# current_monitor_v1-2-1.net
KiCad netlist of a schematic drawn in EAGLE
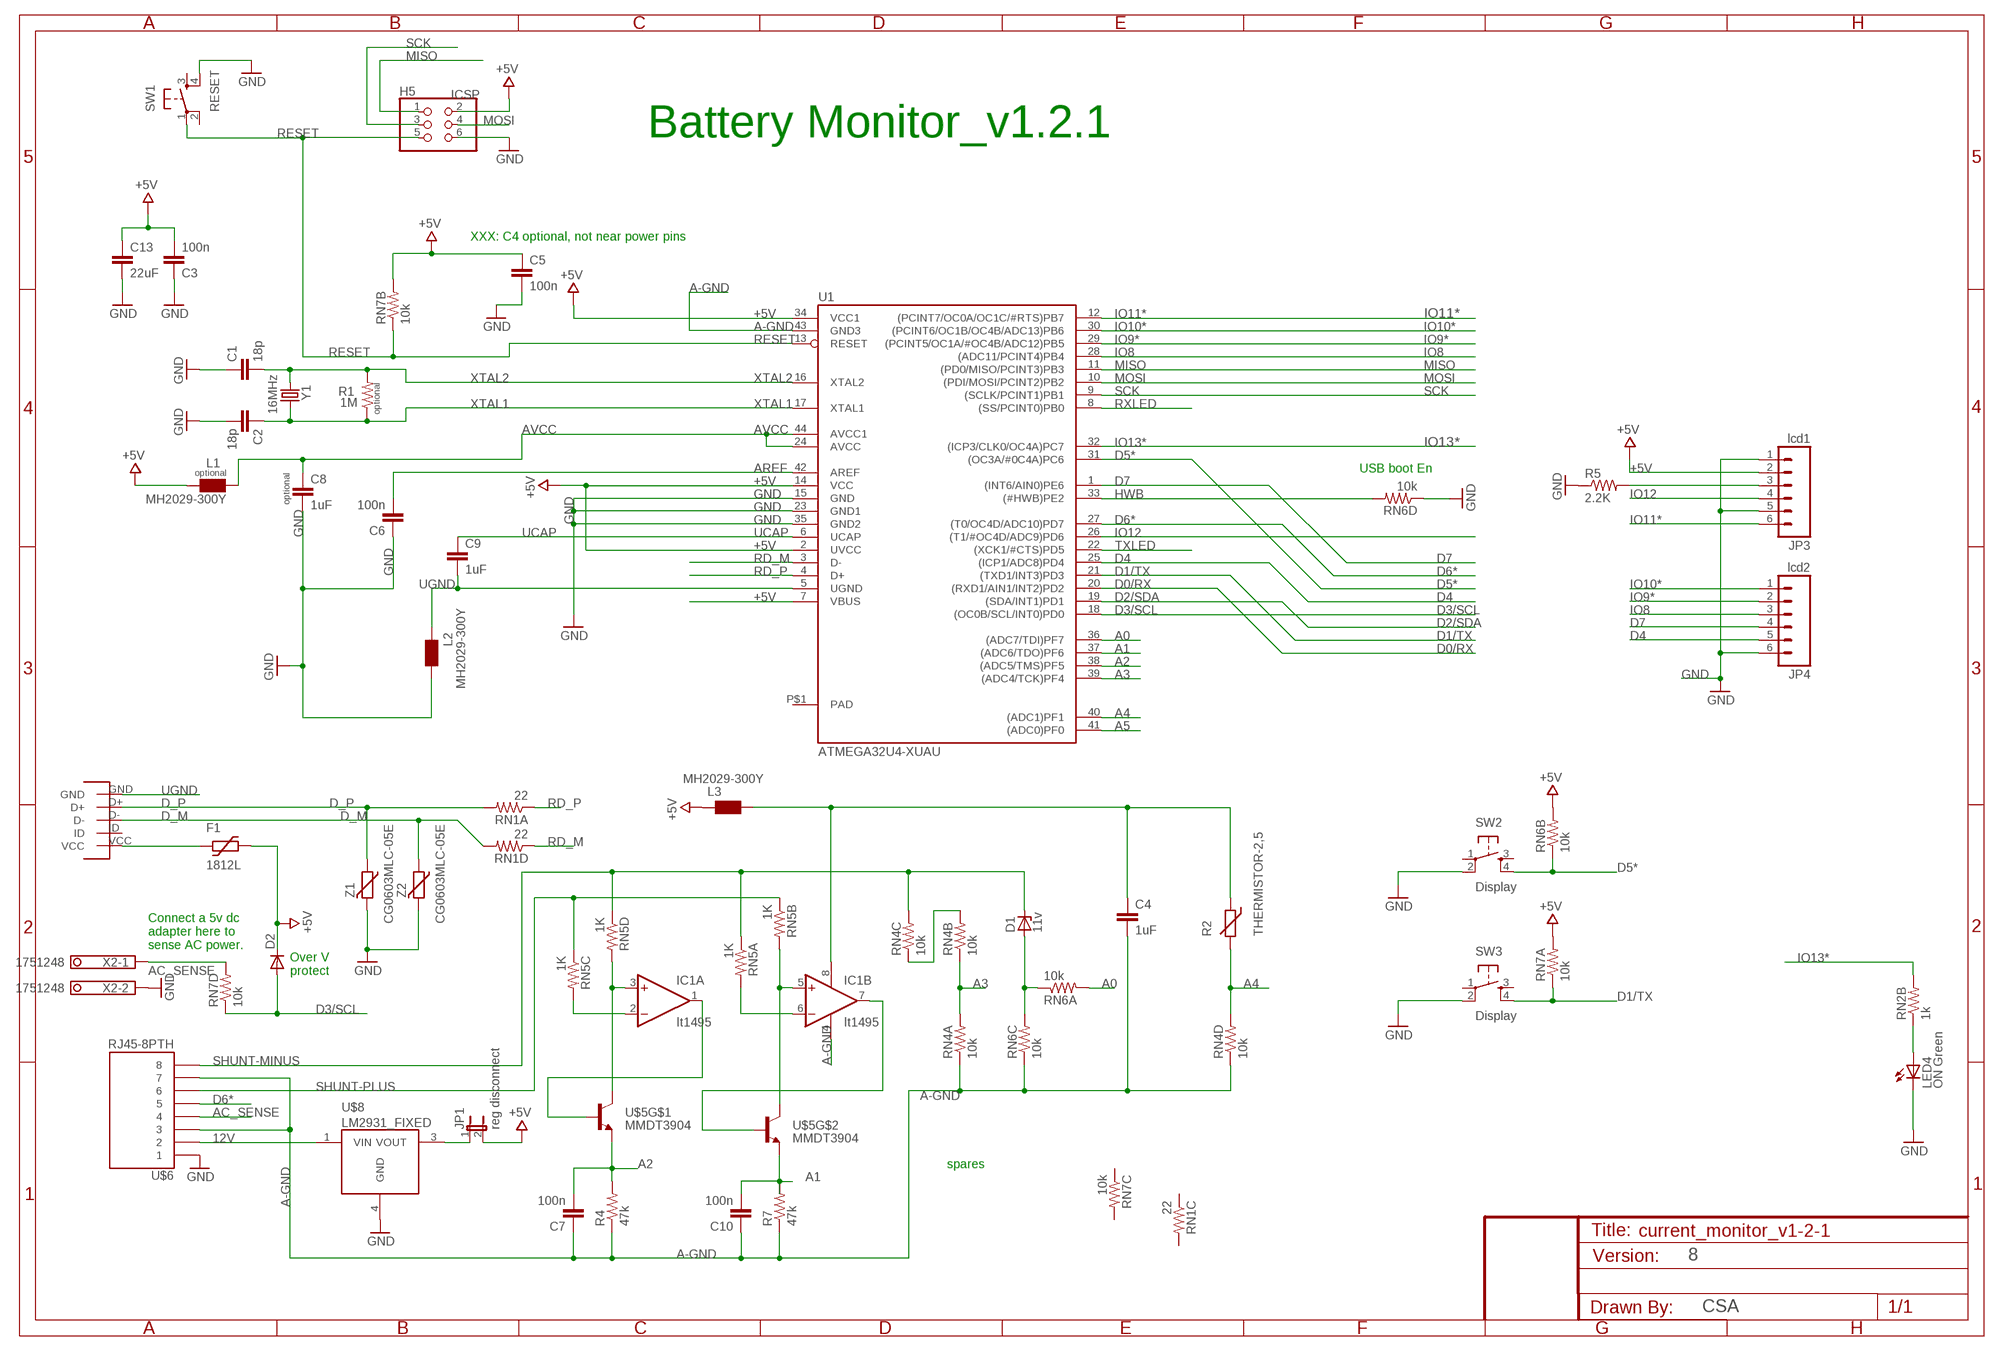
[diagram p0: schematic, sheet 1]

(export (version "E")
  (design (tool "Eeschema 10.0.6"))
  (components
    (comp (ref "C1")
      (value "18p")
      (footprint "eagle-import:0805")
      (libsource (lib "eagle-import") (part "CAP0805"))
    )
    (comp (ref "C2")
      (value "18p")
      (footprint "eagle-import:0805")
      (libsource (lib "eagle-import") (part "CAP0805"))
    )
    (comp (ref "C3")
      (value "100n")
      (footprint "eagle-import:0805")
      (libsource (lib "eagle-import") (part "CAP0805"))
    )
    (comp (ref "C4")
      (value "1uF")
      (footprint "eagle-import:0805")
      (libsource (lib "eagle-import") (part "CAP0805"))
    )
    (comp (ref "C5")
      (value "100n")
      (footprint "eagle-import:0805")
      (libsource (lib "eagle-import") (part "CAP0805"))
    )
    (comp (ref "C6")
      (value "100n")
      (footprint "eagle-import:0805")
      (libsource (lib "eagle-import") (part "CAP0805"))
    )
    (comp (ref "C7")
      (value "100n")
      (footprint "eagle-import:0805")
      (libsource (lib "eagle-import") (part "CAP0805"))
    )
    (comp (ref "C8")
      (value "1uF")
      (footprint "eagle-import:0805")
      (libsource (lib "eagle-import") (part "CAP0805"))
    )
    (comp (ref "C9")
      (value "1uF")
      (footprint "eagle-import:0805")
      (libsource (lib "eagle-import") (part "CAP0805"))
    )
    (comp (ref "C10")
      (value "100n")
      (footprint "eagle-import:0805")
      (libsource (lib "eagle-import") (part "CAP0805"))
    )
    (comp (ref "C13")
      (value "22uF")
      (footprint "eagle-import:1206")
      (libsource (lib "eagle-import") (part "CAP1206"))
    )
    (comp (ref "D1")
      (value "11v")
      (footprint "eagle-import:ZDIO-5")
      (libsource (lib "eagle-import") (part "ZENER-DIODEZD-5"))
    )
    (comp (ref "D2")
      (value "DIODESMA")
      (footprint "eagle-import:SMA-DIODE")
      (libsource (lib "eagle-import") (part "DIODESMA"))
    )
    (comp (ref "F1")
      (value "1812L")
      (footprint "eagle-import:1812L")
      (libsource (lib "eagle-import") (part "1812L"))
    )
    (comp (ref "H5")
      (value "ICSP")
      (footprint "eagle-import:2X03")
      (libsource (lib "eagle-import") (part "PINHD-2X3"))
    )
    (comp (ref "IC1")
      (value "lt1495")
      (footprint "eagle-import:SO08")
      (libsource (lib "eagle-import") (part "4558DLM"))
    )
    (comp (ref "JP1")
      (value "reg disconnect")
      (footprint "eagle-import:1X02_LOCK")
      (libsource (lib "eagle-import") (part "JUMPER-2-OLDPTH_LOCK"))
    )
    (comp (ref "JP3")
      (value "lcd1")
      (footprint "eagle-import:1X06_FEMALE_LOCK.010")
      (libsource (lib "eagle-import") (part "M06FEMALE_LOCK"))
    )
    (comp (ref "JP4")
      (value "lcd2")
      (footprint "eagle-import:1X06_FEMALE_LOCK.010")
      (libsource (lib "eagle-import") (part "M06FEMALE_LOCK"))
    )
    (comp (ref "L1")
      (value "MH2029-300Y")
      (footprint "eagle-import:0805")
      (libsource (lib "eagle-import") (part "WE-CBF_0805"))
    )
    (comp (ref "L2")
      (value "MH2029-300Y")
      (footprint "eagle-import:0805")
      (libsource (lib "eagle-import") (part "WE-CBF_0805"))
    )
    (comp (ref "L3")
      (value "MH2029-300Y")
      (footprint "eagle-import:0805")
      (libsource (lib "eagle-import") (part "WE-CBF_0805"))
    )
    (comp (ref "LED4")
      (value "ON Green")
      (footprint "eagle-import:LED0805")
      (libsource (lib "eagle-import") (part "LED0805"))
    )
    (comp (ref "R1")
      (value "1M")
      (footprint "eagle-import:0805")
      (libsource (lib "eagle-import") (part "RESISTOR0805-RES"))
    )
    (comp (ref "R2")
      (value "THERMISTOR-2,5")
      (footprint "eagle-import:RS-2,5")
      (libsource (lib "eagle-import") (part "THERMISTOR-2,5"))
    )
    (comp (ref "R4")
      (value "47k")
      (footprint "eagle-import:0805")
      (libsource (lib "eagle-import") (part "RESISTOR0805-RES"))
    )
    (comp (ref "R5")
      (value "2.2K")
      (footprint "eagle-import:0805")
      (libsource (lib "eagle-import") (part "RESISTOR0805-RES"))
    )
    (comp (ref "R7")
      (value "47k")
      (footprint "eagle-import:0805")
      (libsource (lib "eagle-import") (part "RESISTOR0805-RES"))
    )
    (comp (ref "RN1")
      (value "22")
      (footprint "eagle-import:CRA06S")
      (libsource (lib "eagle-import") (part "RESISTOR-ARRAYCRA06S"))
    )
    (comp (ref "RN2")
      (value "1k")
      (footprint "eagle-import:CRA06S")
      (libsource (lib "eagle-import") (part "RESISTOR-ARRAYCRA06S"))
    )
    (comp (ref "RN4")
      (value "10k")
      (footprint "eagle-import:CRA06S")
      (libsource (lib "eagle-import") (part "RESISTOR-ARRAYCRA06S"))
    )
    (comp (ref "RN5")
      (value "1K")
      (footprint "eagle-import:CRA06S")
      (libsource (lib "eagle-import") (part "RESISTOR-ARRAYCRA06S"))
    )
    (comp (ref "RN6")
      (value "10k")
      (footprint "eagle-import:CRA06S")
      (libsource (lib "eagle-import") (part "RESISTOR-ARRAYCRA06S"))
    )
    (comp (ref "RN7")
      (value "10k")
      (footprint "eagle-import:CRA06S")
      (libsource (lib "eagle-import") (part "RESISTOR-ARRAYCRA06S"))
    )
    (comp (ref "SW1")
      (value "RESET")
      (footprint "eagle-import:TACTILE-PTH")
      (libsource (lib "eagle-import") (part "TAC_SWITCHPTH"))
    )
    (comp (ref "SW2")
      (value "Display")
      (footprint "eagle-import:TACTILE-PTH")
      (libsource (lib "eagle-import") (part "TAC_SWITCHPTH"))
    )
    (comp (ref "SW3")
      (value "Display")
      (footprint "eagle-import:TACTILE-PTH")
      (libsource (lib "eagle-import") (part "TAC_SWITCHPTH"))
    )
    (comp (ref "U$5")
      (value "MMDT3904")
      (footprint "eagle-import:SOT363")
      (libsource (lib "eagle-import") (part "MMDT3904"))
    )
    (comp (ref "U$6")
      (value "RJ45-8PTH")
      (footprint "eagle-import:RJ45-8")
      (libsource (lib "eagle-import") (part "RJ45-8PTH"))
    )
    (comp (ref "U$8")
      (value "LM2931_FIXED")
      (footprint "eagle-import:DPAK")
      (libsource (lib "eagle-import") (part "LM2931_FIXED"))
    )
    (comp (ref "U$16")
      (value "USB-MICRO-B-DIGIKEY")
      (footprint "eagle-import:USB-MICRO-B-DIGIKEY")
      (libsource (lib "eagle-import") (part "USB-MICRO-B-DIGIKEY"))
    )
    (comp (ref "U1")
      (value "ATMEGA32U4-XUAU")
      (footprint "eagle-import:TQFP44-PAD")
      (libsource (lib "eagle-import") (part "ATMEGA32U4-XUAU"))
    )
    (comp (ref "X2")
      (value "1751248")
      (footprint "eagle-import:1751248")
      (libsource (lib "eagle-import") (part "1751248"))
    )
    (comp (ref "Y1")
      (value "16MHz")
      (footprint "eagle-import:HC49US")
      (libsource (lib "eagle-import") (part "CRYSTALHC49US"))
    )
    (comp (ref "Z1")
      (value "CG0603MLC-05E")
      (footprint "eagle-import:CT_CN0603")
      (libsource (lib "eagle-import") (part "VARISTORCN0603"))
    )
    (comp (ref "Z2")
      (value "CG0603MLC-05E")
      (footprint "eagle-import:CT_CN0603")
      (libsource (lib "eagle-import") (part "VARISTORCN0603"))
    )
  )
  (nets
    (net (code "1") (name "+5V") (class "Default")
      (node (ref "C13") (pin "1") (pinfunction "1_1") (pintype "passive"))
      (node (ref "C3") (pin "2") (pinfunction "2_2") (pintype "passive"))
      (node (ref "C5") (pin "1") (pinfunction "1_1") (pintype "passive"))
      (node (ref "D2") (pin "C") (pinfunction "C_C") (pintype "passive"))
      (node (ref "F1") (pin "P$2") (pinfunction "2_P$2") (pintype "passive"))
      (node (ref "H5") (pin "2") (pinfunction "2_2") (pintype "passive"))
      (node (ref "JP1") (pin "2") (pinfunction "2_2") (pintype "passive"))
      (node (ref "JP3") (pin "2") (pinfunction "2_2") (pintype "passive"))
      (node (ref "L1") (pin "1") (pinfunction "1_1") (pintype "passive"))
      (node (ref "L3") (pin "1") (pinfunction "1_1") (pintype "passive"))
      (node (ref "RN6") (pin "7") (pinfunction "2_7") (pintype "passive"))
      (node (ref "RN7") (pin "7") (pinfunction "2_7") (pintype "passive"))
      (node (ref "RN7") (pin "8") (pinfunction "2_8") (pintype "passive"))
      (node (ref "U1") (pin "14") (pinfunction "VCC_14") (pintype "power_in"))
      (node (ref "U1") (pin "2") (pinfunction "UVCC_2") (pintype "power_in"))
      (node (ref "U1") (pin "34") (pinfunction "VCC1_34") (pintype "power_in"))
      (node (ref "U1") (pin "7") (pinfunction "VBUS_7") (pintype "input"))
    )
    (net (code "2") (name "/12V") (class "Default")
      (node (ref "U$6") (pin "2") (pinfunction "2_2") (pintype "bidirectional"))
      (node (ref "U$8") (pin "1") (pinfunction "VIN_1") (pintype "bidirectional"))
    )
    (net (code "3") (name "/A-GND") (class "Default")
      (node (ref "C10") (pin "1") (pinfunction "1_1") (pintype "passive"))
      (node (ref "C4") (pin "2") (pinfunction "2_2") (pintype "passive"))
      (node (ref "C7") (pin "1") (pinfunction "1_1") (pintype "passive"))
      (node (ref "IC1") (pin "4") (pinfunction "V-_4") (pintype "power_in"))
      (node (ref "R4") (pin "1") (pinfunction "1_1") (pintype "passive"))
      (node (ref "R7") (pin "1") (pinfunction "1_1") (pintype "passive"))
      (node (ref "RN4") (pin "1") (pinfunction "1_1") (pintype "passive"))
      (node (ref "RN4") (pin "4") (pinfunction "1_4") (pintype "passive"))
      (node (ref "RN6") (pin "3") (pinfunction "1_3") (pintype "passive"))
      (node (ref "U$6") (pin "3") (pinfunction "3_3") (pintype "bidirectional"))
      (node (ref "U$6") (pin "7") (pinfunction "7_7") (pintype "bidirectional"))
      (node (ref "U1") (pin "43") (pinfunction "GND3_43") (pintype "power_in"))
    )
    (net (code "4") (name "/A0") (class "Default")
      (node (ref "RN6") (pin "8") (pinfunction "2_8") (pintype "passive"))
      (node (ref "U1") (pin "36") (pinfunction "(ADC7/TDI)PF7_36") (pintype "bidirectional"))
    )
    (net (code "5") (name "/A1") (class "Default")
      (node (ref "C10") (pin "2") (pinfunction "2_2") (pintype "passive"))
      (node (ref "R7") (pin "2") (pinfunction "2_2") (pintype "passive"))
      (node (ref "U$5") (pin "1") (pinfunction "E_1") (pintype "passive"))
      (node (ref "U1") (pin "37") (pinfunction "(ADC6/TDO)PF6_37") (pintype "bidirectional"))
    )
    (net (code "6") (name "/A2") (class "Default")
      (node (ref "C7") (pin "2") (pinfunction "2_2") (pintype "passive"))
      (node (ref "R4") (pin "2") (pinfunction "2_2") (pintype "passive"))
      (node (ref "U$5") (pin "4") (pinfunction "E_4") (pintype "passive"))
      (node (ref "U1") (pin "38") (pinfunction "(ADC5/TMS)PF5_38") (pintype "bidirectional"))
    )
    (net (code "7") (name "/A3") (class "Default")
      (node (ref "RN4") (pin "2") (pinfunction "1_2") (pintype "passive"))
      (node (ref "RN4") (pin "8") (pinfunction "2_8") (pintype "passive"))
      (node (ref "U1") (pin "39") (pinfunction "(ADC4/TCK)PF4_39") (pintype "bidirectional"))
    )
    (net (code "8") (name "/A4") (class "Default")
      (node (ref "R2") (pin "2") (pinfunction "2_2") (pintype "passive"))
      (node (ref "RN4") (pin "5") (pinfunction "2_5") (pintype "passive"))
      (node (ref "U1") (pin "40") (pinfunction "(ADC1)PF1_40") (pintype "bidirectional"))
    )
    (net (code "9") (name "/A5") (class "Default")
      (node (ref "U1") (pin "41") (pinfunction "(ADC0)PF0_41") (pintype "bidirectional"))
    )
    (net (code "10") (name "/AC_SENSE") (class "Default")
      (node (ref "RN7") (pin "5") (pinfunction "2_5") (pintype "passive"))
      (node (ref "U$6") (pin "4") (pinfunction "4_4") (pintype "bidirectional"))
      (node (ref "X2") (pin "1") (pinfunction "K_1") (pintype "passive"))
    )
    (net (code "11") (name "/AREF") (class "Default")
      (node (ref "C6") (pin "2") (pinfunction "2_2") (pintype "passive"))
      (node (ref "U1") (pin "42") (pinfunction "AREF_42") (pintype "power_in"))
    )
    (net (code "12") (name "/AVCC") (class "Default")
      (node (ref "C8") (pin "1") (pinfunction "1_1") (pintype "passive"))
      (node (ref "L1") (pin "2") (pinfunction "2_2") (pintype "passive"))
      (node (ref "U1") (pin "24") (pinfunction "AVCC_24") (pintype "power_in"))
      (node (ref "U1") (pin "44") (pinfunction "AVCC1_44") (pintype "power_in"))
    )
    (net (code "13") (name "/D0{slash}RX") (class "Default")
      (node (ref "U1") (pin "20") (pinfunction "(RXD1/AIN1/INT2)PD2_20") (pintype "bidirectional"))
    )
    (net (code "14") (name "/D1{slash}TX") (class "Default")
      (node (ref "RN7") (pin "1") (pinfunction "1_1") (pintype "passive"))
      (node (ref "SW3") (pin "4") (pinfunction "4_4") (pintype "passive"))
      (node (ref "U1") (pin "21") (pinfunction "(TXD1/INT3)PD3_21") (pintype "bidirectional"))
    )
    (net (code "15") (name "/D2{slash}SDA") (class "Default")
      (node (ref "U1") (pin "19") (pinfunction "(SDA/INT1)PD1_19") (pintype "bidirectional"))
    )
    (net (code "16") (name "/D3{slash}SCL") (class "Default")
      (node (ref "D2") (pin "A") (pinfunction "A_A") (pintype "passive"))
      (node (ref "RN7") (pin "4") (pinfunction "1_4") (pintype "passive"))
      (node (ref "U1") (pin "18") (pinfunction "(OC0B/SCL/INT0)PD0_18") (pintype "bidirectional"))
    )
    (net (code "17") (name "/D4") (class "Default")
      (node (ref "JP4") (pin "5") (pinfunction "5_5") (pintype "passive"))
      (node (ref "U1") (pin "25") (pinfunction "(ICP1/ADC8)PD4_25") (pintype "bidirectional"))
    )
    (net (code "18") (name "/D5*") (class "Default")
      (node (ref "RN6") (pin "2") (pinfunction "1_2") (pintype "passive"))
      (node (ref "SW2") (pin "4") (pinfunction "4_4") (pintype "passive"))
      (node (ref "U1") (pin "31") (pinfunction "(OC3A/#0C4A)PC6_31") (pintype "bidirectional"))
    )
    (net (code "19") (name "/D6*") (class "Default")
      (node (ref "U$6") (pin "5") (pinfunction "5_5") (pintype "bidirectional"))
      (node (ref "U1") (pin "27") (pinfunction "(T0/OC4D/ADC10)PD7_27") (pintype "bidirectional"))
    )
    (net (code "20") (name "/D7") (class "Default")
      (node (ref "JP4") (pin "4") (pinfunction "4_4") (pintype "passive"))
      (node (ref "U1") (pin "1") (pinfunction "(INT6/AIN0)PE6_1") (pintype "bidirectional"))
    )
    (net (code "21") (name "/D_M") (class "Default")
      (node (ref "RN1") (pin "5") (pinfunction "2_5") (pintype "passive"))
      (node (ref "U$16") (pin "D-") (pinfunction "D-_D-") (pintype "bidirectional"))
      (node (ref "Z2") (pin "1") (pinfunction "1_1") (pintype "passive"))
    )
    (net (code "22") (name "/D_P") (class "Default")
      (node (ref "RN1") (pin "8") (pinfunction "2_8") (pintype "passive"))
      (node (ref "U$16") (pin "D+") (pinfunction "D+_D+") (pintype "bidirectional"))
      (node (ref "Z1") (pin "1") (pinfunction "1_1") (pintype "passive"))
    )
    (net (code "23") (name "/HWB") (class "Default")
      (node (ref "RN6") (pin "5") (pinfunction "2_5") (pintype "passive"))
      (node (ref "U1") (pin "33") (pinfunction "(#HWB)PE2_33") (pintype "bidirectional"))
    )
    (net (code "24") (name "/IO8") (class "Default")
      (node (ref "JP4") (pin "3") (pinfunction "3_3") (pintype "passive"))
      (node (ref "U1") (pin "28") (pinfunction "(ADC11/PCINT4)PB4_28") (pintype "bidirectional"))
    )
    (net (code "25") (name "/IO9*") (class "Default")
      (node (ref "JP4") (pin "2") (pinfunction "2_2") (pintype "passive"))
      (node (ref "U1") (pin "29") (pinfunction "(PCINT5/OC1A/#OC4B/ADC12)PB5_29") (pintype "bidirectional"))
    )
    (net (code "26") (name "/IO10*") (class "Default")
      (node (ref "JP4") (pin "1") (pinfunction "1_1") (pintype "passive"))
      (node (ref "U1") (pin "30") (pinfunction "(PCINT6/OC1B/OC4B/ADC13)PB6_30") (pintype "bidirectional"))
    )
    (net (code "27") (name "/IO11*") (class "Default")
      (node (ref "JP3") (pin "6") (pinfunction "6_6") (pintype "passive"))
      (node (ref "U1") (pin "12") (pinfunction "(PCINT7/OC0A/OC1C/#RTS)PB7_12") (pintype "bidirectional"))
    )
    (net (code "28") (name "/IO12") (class "Default")
      (node (ref "JP3") (pin "4") (pinfunction "4_4") (pintype "passive"))
      (node (ref "U1") (pin "26") (pinfunction "(T1/#OC4D/ADC9)PD6_26") (pintype "bidirectional"))
    )
    (net (code "29") (name "/IO13*") (class "Default")
      (node (ref "RN2") (pin "7") (pinfunction "2_7") (pintype "passive"))
      (node (ref "U1") (pin "32") (pinfunction "(ICP3/CLK0/OC4A)PC7_32") (pintype "bidirectional"))
    )
    (net (code "30") (name "/MISO") (class "Default")
      (node (ref "H5") (pin "1") (pinfunction "1_1") (pintype "passive"))
      (node (ref "U1") (pin "11") (pinfunction "(PD0/MISO/PCINT3)PB3_11") (pintype "bidirectional"))
    )
    (net (code "31") (name "/MOSI") (class "Default")
      (node (ref "H5") (pin "4") (pinfunction "4_4") (pintype "passive"))
      (node (ref "U1") (pin "10") (pinfunction "(PDI/MOSI/PCINT2)PB2_10") (pintype "bidirectional"))
    )
    (net (code "32") (name "/PAD") (class "Default")
      (node (ref "U1") (pin "P$1") (pinfunction "PAD_P$1") (pintype "power_in"))
    )
    (net (code "33") (name "/RD_M") (class "Default")
      (node (ref "RN1") (pin "4") (pinfunction "1_4") (pintype "passive"))
      (node (ref "U1") (pin "3") (pinfunction "D-_3") (pintype "bidirectional"))
    )
    (net (code "34") (name "/RD_P") (class "Default")
      (node (ref "RN1") (pin "1") (pinfunction "1_1") (pintype "passive"))
      (node (ref "U1") (pin "4") (pinfunction "D+_4") (pintype "bidirectional"))
    )
    (net (code "35") (name "/RESET") (class "Default")
      (node (ref "H5") (pin "5") (pinfunction "5_5") (pintype "passive"))
      (node (ref "RN7") (pin "2") (pinfunction "1_2") (pintype "passive"))
      (node (ref "SW1") (pin "1") (pinfunction "1_1") (pintype "passive"))
      (node (ref "U1") (pin "13") (pinfunction "RESET_13") (pintype "input"))
    )
    (net (code "36") (name "/RXLED") (class "Default")
      (node (ref "U1") (pin "8") (pinfunction "(SS/PCINT0)PB0_8") (pintype "bidirectional"))
    )
    (net (code "37") (name "/SCK") (class "Default")
      (node (ref "H5") (pin "3") (pinfunction "3_3") (pintype "passive"))
      (node (ref "U1") (pin "9") (pinfunction "(SCLK/PCINT1)PB1_9") (pintype "bidirectional"))
    )
    (net (code "38") (name "/SHUNT-MINUS") (class "Default")
      (node (ref "D1") (pin "C") (pinfunction "C_C") (pintype "passive"))
      (node (ref "RN4") (pin "6") (pinfunction "2_6") (pintype "passive"))
      (node (ref "RN5") (pin "1") (pinfunction "1_1") (pintype "passive"))
      (node (ref "RN5") (pin "4") (pinfunction "1_4") (pintype "passive"))
      (node (ref "U$6") (pin "8") (pinfunction "8_8") (pintype "bidirectional"))
    )
    (net (code "39") (name "/SHUNT-PLUS") (class "Default")
      (node (ref "RN5") (pin "2") (pinfunction "1_2") (pintype "passive"))
      (node (ref "RN5") (pin "3") (pinfunction "1_3") (pintype "passive"))
      (node (ref "U$6") (pin "6") (pinfunction "6_6") (pintype "bidirectional"))
    )
    (net (code "40") (name "/TXLED") (class "Default")
      (node (ref "U1") (pin "22") (pinfunction "(XCK1/#CTS)PD5_22") (pintype "bidirectional"))
    )
    (net (code "41") (name "/UCAP") (class "Default")
      (node (ref "C9") (pin "1") (pinfunction "1_1") (pintype "passive"))
      (node (ref "U1") (pin "6") (pinfunction "UCAP_6") (pintype "passive"))
    )
    (net (code "42") (name "/UGND") (class "Default")
      (node (ref "C9") (pin "2") (pinfunction "2_2") (pintype "passive"))
      (node (ref "L2") (pin "1") (pinfunction "1_1") (pintype "passive"))
      (node (ref "U$16") (pin "GND") (pinfunction "GND_GND") (pintype "bidirectional"))
      (node (ref "U1") (pin "5") (pinfunction "UGND_5") (pintype "power_in"))
    )
    (net (code "43") (name "/XTAL1") (class "Default")
      (node (ref "C2") (pin "1") (pinfunction "1_1") (pintype "passive"))
      (node (ref "R1") (pin "1") (pinfunction "1_1") (pintype "passive"))
      (node (ref "U1") (pin "17") (pinfunction "XTAL1_17") (pintype "bidirectional"))
      (node (ref "Y1") (pin "2") (pinfunction "2_2") (pintype "passive"))
    )
    (net (code "44") (name "/XTAL2") (class "Default")
      (node (ref "C1") (pin "2") (pinfunction "2_2") (pintype "passive"))
      (node (ref "R1") (pin "2") (pinfunction "2_2") (pintype "passive"))
      (node (ref "U1") (pin "16") (pinfunction "XTAL2_16") (pintype "bidirectional"))
      (node (ref "Y1") (pin "1") (pinfunction "1_1") (pintype "passive"))
    )
    (net (code "45") (name "GND") (class "Default")
      (node (ref "C1") (pin "1") (pinfunction "1_1") (pintype "passive"))
      (node (ref "C13") (pin "2") (pinfunction "2_2") (pintype "passive"))
      (node (ref "C2") (pin "2") (pinfunction "2_2") (pintype "passive"))
      (node (ref "C3") (pin "1") (pinfunction "1_1") (pintype "passive"))
      (node (ref "C5") (pin "2") (pinfunction "2_2") (pintype "passive"))
      (node (ref "C6") (pin "1") (pinfunction "1_1") (pintype "passive"))
      (node (ref "C8") (pin "2") (pinfunction "2_2") (pintype "passive"))
      (node (ref "H5") (pin "6") (pinfunction "6_6") (pintype "passive"))
      (node (ref "JP3") (pin "1") (pinfunction "1_1") (pintype "passive"))
      (node (ref "JP3") (pin "5") (pinfunction "5_5") (pintype "passive"))
      (node (ref "JP4") (pin "6") (pinfunction "6_6") (pintype "passive"))
      (node (ref "L2") (pin "2") (pinfunction "2_2") (pintype "passive"))
      (node (ref "LED4") (pin "C") (pinfunction "C_C") (pintype "passive"))
      (node (ref "R5") (pin "1") (pinfunction "1_1") (pintype "passive"))
      (node (ref "RN6") (pin "4") (pinfunction "1_4") (pintype "passive"))
      (node (ref "SW1") (pin "4") (pinfunction "4_4") (pintype "passive"))
      (node (ref "SW2") (pin "2") (pinfunction "2_2") (pintype "passive"))
      (node (ref "SW3") (pin "2") (pinfunction "2_2") (pintype "passive"))
      (node (ref "U$6") (pin "1") (pinfunction "1_1") (pintype "bidirectional"))
      (node (ref "U$8") (pin "4") (pinfunction "GND_4") (pintype "bidirectional"))
      (node (ref "U1") (pin "15") (pinfunction "GND_15") (pintype "power_in"))
      (node (ref "U1") (pin "23") (pinfunction "GND1_23") (pintype "power_in"))
      (node (ref "U1") (pin "35") (pinfunction "GND2_35") (pintype "power_in"))
      (node (ref "X2") (pin "2") (pinfunction "K_2") (pintype "passive"))
      (node (ref "Z1") (pin "2") (pinfunction "2_2") (pintype "passive"))
      (node (ref "Z2") (pin "2") (pinfunction "2_2") (pintype "passive"))
    )
    (net (code "46") (name "Net-(F1-1)") (class "Default")
      (node (ref "F1") (pin "P$1") (pinfunction "1_P$1") (pintype "passive"))
      (node (ref "U$16") (pin "VCC") (pinfunction "VCC_VCC") (pintype "bidirectional"))
    )
    (net (code "47") (name "Net-(IC1A-+IN)") (class "Default")
      (node (ref "IC1") (pin "3") (pinfunction "+IN_3") (pintype "input"))
      (node (ref "RN5") (pin "5") (pinfunction "2_5") (pintype "passive"))
      (node (ref "U$5") (pin "3") (pinfunction "C_3") (pintype "passive"))
    )
    (net (code "48") (name "Net-(IC1A--IN)") (class "Default")
      (node (ref "IC1") (pin "2") (pinfunction "-IN_2") (pintype "input"))
      (node (ref "RN5") (pin "6") (pinfunction "2_6") (pintype "passive"))
    )
    (net (code "49") (name "Net-(IC1A-OUT)") (class "Default")
      (node (ref "IC1") (pin "1") (pinfunction "OUT_1") (pintype "output"))
      (node (ref "U$5") (pin "5") (pinfunction "B_5") (pintype "passive"))
    )
    (net (code "50") (name "Net-(IC1B-+IN)") (class "Default")
      (node (ref "IC1") (pin "5") (pinfunction "+IN_5") (pintype "input"))
      (node (ref "RN5") (pin "7") (pinfunction "2_7") (pintype "passive"))
      (node (ref "U$5") (pin "6") (pinfunction "C_6") (pintype "passive"))
    )
    (net (code "51") (name "Net-(IC1B--IN)") (class "Default")
      (node (ref "IC1") (pin "6") (pinfunction "-IN_6") (pintype "input"))
      (node (ref "RN5") (pin "8") (pinfunction "2_8") (pintype "passive"))
    )
    (net (code "52") (name "Net-(IC1B-OUT)") (class "Default")
      (node (ref "IC1") (pin "7") (pinfunction "OUT_7") (pintype "output"))
      (node (ref "U$5") (pin "2") (pinfunction "B_2") (pintype "passive"))
    )
    (net (code "53") (name "Net-(IC1C-V+)") (class "Default")
      (node (ref "C4") (pin "1") (pinfunction "1_1") (pintype "passive"))
      (node (ref "IC1") (pin "8") (pinfunction "V+_8") (pintype "power_in"))
      (node (ref "L3") (pin "2") (pinfunction "2_2") (pintype "passive"))
      (node (ref "R2") (pin "1") (pinfunction "1_1") (pintype "passive"))
    )
    (net (code "54") (name "Net-(JP3-Pad3)") (class "Default")
      (node (ref "JP3") (pin "3") (pinfunction "3_3") (pintype "passive"))
      (node (ref "R5") (pin "2") (pinfunction "2_2") (pintype "passive"))
    )
    (net (code "55") (name "Net-(RN2B-1)") (class "Default")
      (node (ref "LED4") (pin "A") (pinfunction "A_A") (pintype "passive"))
      (node (ref "RN2") (pin "2") (pinfunction "1_2") (pintype "passive"))
    )
    (net (code "56") (name "Net-(RN4B-2)") (class "Default")
      (node (ref "RN4") (pin "3") (pinfunction "1_3") (pintype "passive"))
      (node (ref "RN4") (pin "7") (pinfunction "2_7") (pintype "passive"))
    )
    (net (code "57") (name "Net-(RN6C-2)") (class "Default")
      (node (ref "D1") (pin "A") (pinfunction "A_A") (pintype "passive"))
      (node (ref "RN6") (pin "1") (pinfunction "1_1") (pintype "passive"))
      (node (ref "RN6") (pin "6") (pinfunction "2_6") (pintype "passive"))
    )
    (net (code "58") (name "Net-(U$8-VOUT)") (class "Default")
      (node (ref "JP1") (pin "1") (pinfunction "1_1") (pintype "passive"))
      (node (ref "U$8") (pin "3") (pinfunction "VOUT_3") (pintype "bidirectional"))
    )
    (net (code "59") (name "unconnected-(RN1C-1-Pad3)") (class "Default")
      (node (ref "RN1") (pin "3") (pinfunction "1_3") (pintype "passive"))
    )
    (net (code "60") (name "unconnected-(RN1C-2-Pad6)") (class "Default")
      (node (ref "RN1") (pin "6") (pinfunction "2_6") (pintype "passive"))
    )
    (net (code "61") (name "unconnected-(RN7C-1-Pad3)") (class "Default")
      (node (ref "RN7") (pin "3") (pinfunction "1_3") (pintype "passive"))
    )
    (net (code "62") (name "unconnected-(RN7C-2-Pad6)") (class "Default")
      (node (ref "RN7") (pin "6") (pinfunction "2_6") (pintype "passive"))
    )
    (net (code "63") (name "unconnected-(SW1-Pad2)") (class "Default")
      (node (ref "SW1") (pin "2") (pinfunction "2_2") (pintype "passive"))
    )
    (net (code "64") (name "unconnected-(SW1-Pad3)") (class "Default")
      (node (ref "SW1") (pin "3") (pinfunction "3_3") (pintype "passive"))
    )
    (net (code "65") (name "unconnected-(SW2-Pad1)") (class "Default")
      (node (ref "SW2") (pin "1") (pinfunction "1_1") (pintype "passive"))
    )
    (net (code "66") (name "unconnected-(SW2-Pad3)") (class "Default")
      (node (ref "SW2") (pin "3") (pinfunction "3_3") (pintype "passive"))
    )
    (net (code "67") (name "unconnected-(SW3-Pad1)") (class "Default")
      (node (ref "SW3") (pin "1") (pinfunction "1_1") (pintype "passive"))
    )
    (net (code "68") (name "unconnected-(SW3-Pad3)") (class "Default")
      (node (ref "SW3") (pin "3") (pinfunction "3_3") (pintype "passive"))
    )
    (net (code "69") (name "unconnected-(U$16-PadID)") (class "Default")
      (node (ref "U$16") (pin "ID") (pinfunction "ID_ID") (pintype "bidirectional"))
    )
  )
)
